# Input_scheme.net
KiCad netlist of a schematic drawn in Altium Designer
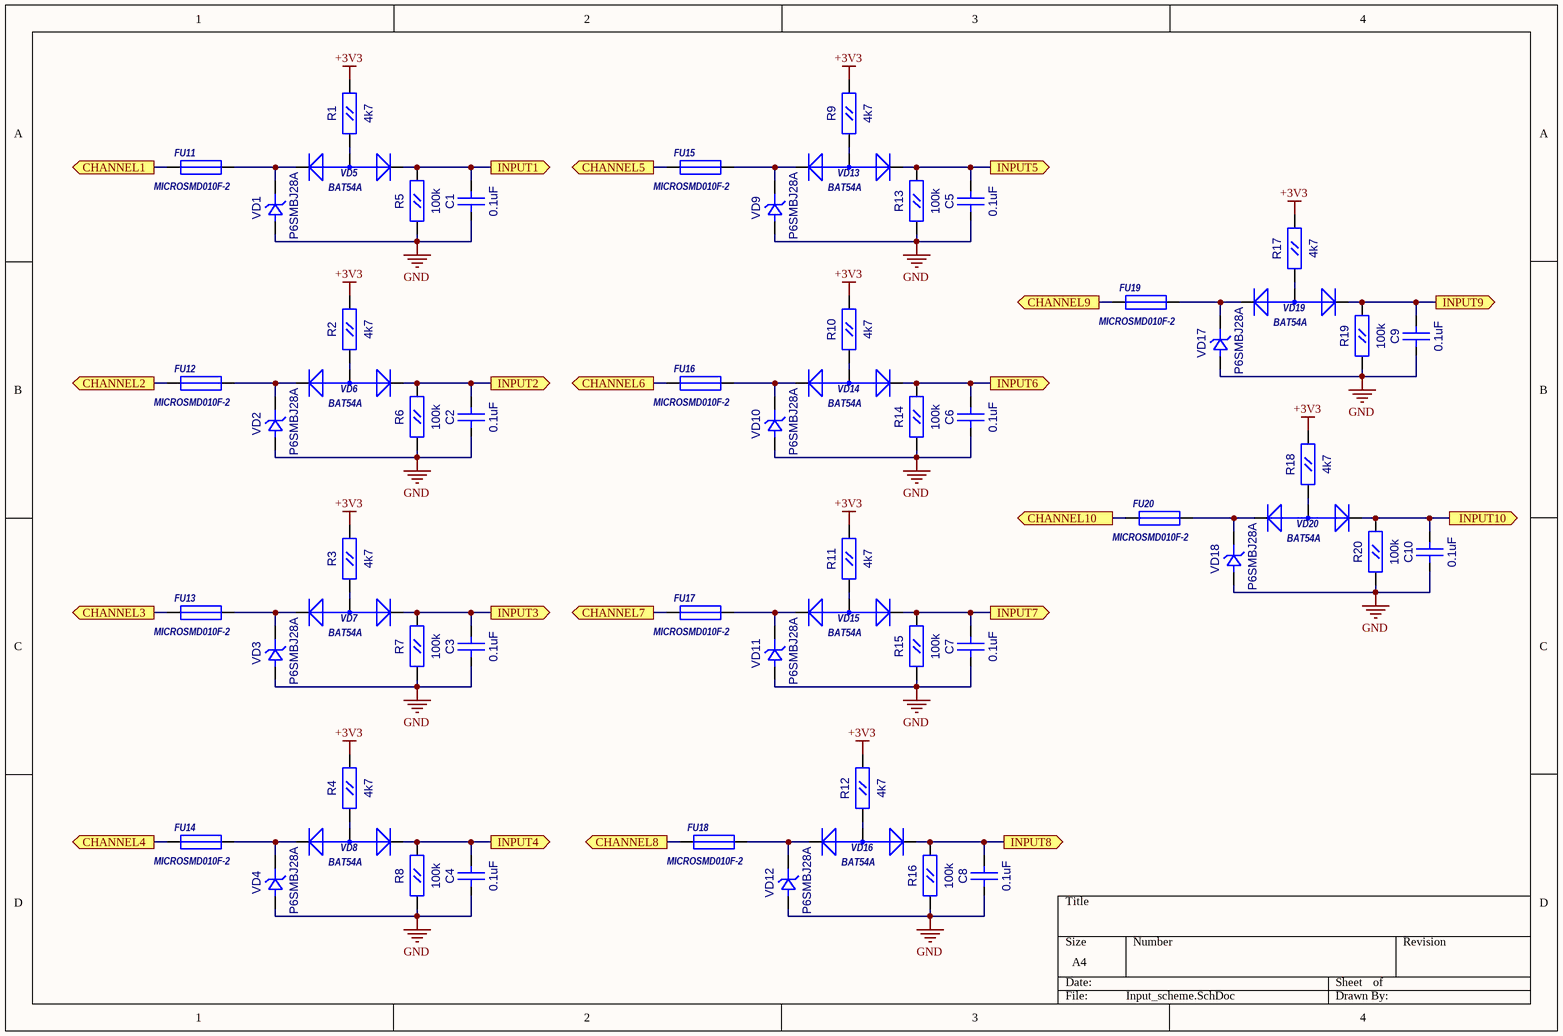
[diagram p0: Input_scheme.SchDoc]

(export (version "E")
  (design (tool "Eeschema 10.0.6"))
  (components
    (comp (ref "C1")
      (value "0.1uF")
      (footprint "CC0603")
      (description "CC0603")
      (libsource (lib "gprs_modem_2") (part "CC0603"))
    )
    (comp (ref "C2")
      (value "0.1uF")
      (footprint "CC0603")
      (description "CC0603")
      (libsource (lib "gprs_modem_2") (part "CC0603"))
    )
    (comp (ref "C3")
      (value "0.1uF")
      (footprint "CC0603")
      (description "CC0603")
      (libsource (lib "gprs_modem_2") (part "CC0603"))
    )
    (comp (ref "C4")
      (value "0.1uF")
      (footprint "CC0603")
      (description "CC0603")
      (libsource (lib "gprs_modem_2") (part "CC0603"))
    )
    (comp (ref "C5")
      (value "0.1uF")
      (footprint "CC0603")
      (description "CC0603")
      (libsource (lib "gprs_modem_2") (part "CC0603"))
    )
    (comp (ref "C6")
      (value "0.1uF")
      (footprint "CC0603")
      (description "CC0603")
      (libsource (lib "gprs_modem_2") (part "CC0603"))
    )
    (comp (ref "C7")
      (value "0.1uF")
      (footprint "CC0603")
      (description "CC0603")
      (libsource (lib "gprs_modem_2") (part "CC0603"))
    )
    (comp (ref "C8")
      (value "0.1uF")
      (footprint "CC0603")
      (description "CC0603")
      (libsource (lib "gprs_modem_2") (part "CC0603"))
    )
    (comp (ref "C9")
      (value "0.1uF")
      (footprint "CC0603")
      (description "CC0603")
      (libsource (lib "gprs_modem_2") (part "CC0603"))
    )
    (comp (ref "C10")
      (value "0.1uF")
      (footprint "CC0603")
      (description "CC0603")
      (libsource (lib "gprs_modem_2") (part "CC0603"))
    )
    (comp (ref "FU11")
      (value "MICROSMD010F-2")
      (footprint "RC1210")
      (description "MICROSMD")
      (libsource (lib "gprs_modem_2") (part "MICROSMD"))
    )
    (comp (ref "FU12")
      (value "MICROSMD010F-2")
      (footprint "RC1210")
      (description "MICROSMD")
      (libsource (lib "gprs_modem_2") (part "MICROSMD"))
    )
    (comp (ref "FU13")
      (value "MICROSMD010F-2")
      (footprint "RC1210")
      (description "MICROSMD")
      (libsource (lib "gprs_modem_2") (part "MICROSMD"))
    )
    (comp (ref "FU14")
      (value "MICROSMD010F-2")
      (footprint "RC1210")
      (description "MICROSMD")
      (libsource (lib "gprs_modem_2") (part "MICROSMD"))
    )
    (comp (ref "FU15")
      (value "MICROSMD010F-2")
      (footprint "RC1210")
      (description "MICROSMD")
      (libsource (lib "gprs_modem_2") (part "MICROSMD"))
    )
    (comp (ref "FU16")
      (value "MICROSMD010F-2")
      (footprint "RC1210")
      (description "MICROSMD")
      (libsource (lib "gprs_modem_2") (part "MICROSMD"))
    )
    (comp (ref "FU17")
      (value "MICROSMD010F-2")
      (footprint "RC1210")
      (description "MICROSMD")
      (libsource (lib "gprs_modem_2") (part "MICROSMD"))
    )
    (comp (ref "FU18")
      (value "MICROSMD010F-2")
      (footprint "RC1210")
      (description "MICROSMD")
      (libsource (lib "gprs_modem_2") (part "MICROSMD"))
    )
    (comp (ref "FU19")
      (value "MICROSMD010F-2")
      (footprint "RC1210")
      (description "MICROSMD")
      (libsource (lib "gprs_modem_2") (part "MICROSMD"))
    )
    (comp (ref "FU20")
      (value "MICROSMD010F-2")
      (footprint "RC1210")
      (description "MICROSMD")
      (libsource (lib "gprs_modem_2") (part "MICROSMD"))
    )
    (comp (ref "R1")
      (value "4k7")
      (footprint "RC0603")
      (description "RC0603")
      (libsource (lib "gprs_modem_2") (part "RC0603"))
    )
    (comp (ref "R2")
      (value "4k7")
      (footprint "RC0603")
      (description "RC0603")
      (libsource (lib "gprs_modem_2") (part "RC0603"))
    )
    (comp (ref "R3")
      (value "4k7")
      (footprint "RC0603")
      (description "RC0603")
      (libsource (lib "gprs_modem_2") (part "RC0603"))
    )
    (comp (ref "R4")
      (value "4k7")
      (footprint "RC0603")
      (description "RC0603")
      (libsource (lib "gprs_modem_2") (part "RC0603"))
    )
    (comp (ref "R5")
      (value "100k")
      (footprint "RC0603")
      (description "RC0603")
      (libsource (lib "gprs_modem_2") (part "RC0603"))
    )
    (comp (ref "R6")
      (value "100k")
      (footprint "RC0603")
      (description "RC0603")
      (libsource (lib "gprs_modem_2") (part "RC0603"))
    )
    (comp (ref "R7")
      (value "100k")
      (footprint "RC0603")
      (description "RC0603")
      (libsource (lib "gprs_modem_2") (part "RC0603"))
    )
    (comp (ref "R8")
      (value "100k")
      (footprint "RC0603")
      (description "RC0603")
      (libsource (lib "gprs_modem_2") (part "RC0603"))
    )
    (comp (ref "R9")
      (value "4k7")
      (footprint "RC0603")
      (description "RC0603")
      (libsource (lib "gprs_modem_2") (part "RC0603"))
    )
    (comp (ref "R10")
      (value "4k7")
      (footprint "RC0603")
      (description "RC0603")
      (libsource (lib "gprs_modem_2") (part "RC0603"))
    )
    (comp (ref "R11")
      (value "4k7")
      (footprint "RC0603")
      (description "RC0603")
      (libsource (lib "gprs_modem_2") (part "RC0603"))
    )
    (comp (ref "R12")
      (value "4k7")
      (footprint "RC0603")
      (description "RC0603")
      (libsource (lib "gprs_modem_2") (part "RC0603"))
    )
    (comp (ref "R13")
      (value "100k")
      (footprint "RC0603")
      (description "RC0603")
      (libsource (lib "gprs_modem_2") (part "RC0603"))
    )
    (comp (ref "R14")
      (value "100k")
      (footprint "RC0603")
      (description "RC0603")
      (libsource (lib "gprs_modem_2") (part "RC0603"))
    )
    (comp (ref "R15")
      (value "100k")
      (footprint "RC0603")
      (description "RC0603")
      (libsource (lib "gprs_modem_2") (part "RC0603"))
    )
    (comp (ref "R16")
      (value "100k")
      (footprint "RC0603")
      (description "RC0603")
      (libsource (lib "gprs_modem_2") (part "RC0603"))
    )
    (comp (ref "R17")
      (value "4k7")
      (footprint "RC0603")
      (description "RC0603")
      (libsource (lib "gprs_modem_2") (part "RC0603"))
    )
    (comp (ref "R18")
      (value "4k7")
      (footprint "RC0603")
      (description "RC0603")
      (libsource (lib "gprs_modem_2") (part "RC0603"))
    )
    (comp (ref "R19")
      (value "100k")
      (footprint "RC0603")
      (description "RC0603")
      (libsource (lib "gprs_modem_2") (part "RC0603"))
    )
    (comp (ref "R20")
      (value "100k")
      (footprint "RC0603")
      (description "RC0603")
      (libsource (lib "gprs_modem_2") (part "RC0603"))
    )
    (comp (ref "VD1")
      (value "P6SMBJ28A")
      (footprint "SMB")
      (description "SMBJ")
      (libsource (lib "gprs_modem") (part "SMBJ"))
    )
    (comp (ref "VD2")
      (value "P6SMBJ28A")
      (footprint "SMB")
      (description "SMBJ")
      (libsource (lib "gprs_modem") (part "SMBJ"))
    )
    (comp (ref "VD3")
      (value "P6SMBJ28A")
      (footprint "SMB")
      (description "SMBJ")
      (libsource (lib "gprs_modem") (part "SMBJ"))
    )
    (comp (ref "VD4")
      (value "P6SMBJ28A")
      (footprint "SMB")
      (description "SMBJ")
      (libsource (lib "gprs_modem") (part "SMBJ"))
    )
    (comp (ref "VD5") (value "BAT54A") (footprint "SOT-23(123)") (libsource (lib "*") (part "BAT54A")))
    (comp (ref "VD6") (value "BAT54A") (footprint "SOT-23(123)") (libsource (lib "*") (part "BAT54A")))
    (comp (ref "VD7") (value "BAT54A") (footprint "SOT-23(123)") (libsource (lib "*") (part "BAT54A")))
    (comp (ref "VD8") (value "BAT54A") (footprint "SOT-23(123)") (libsource (lib "*") (part "BAT54A")))
    (comp (ref "VD9")
      (value "P6SMBJ28A")
      (footprint "SMB")
      (description "SMBJ")
      (libsource (lib "gprs_modem") (part "SMBJ"))
    )
    (comp (ref "VD10")
      (value "P6SMBJ28A")
      (footprint "SMB")
      (description "SMBJ")
      (libsource (lib "gprs_modem") (part "SMBJ"))
    )
    (comp (ref "VD11")
      (value "P6SMBJ28A")
      (footprint "SMB")
      (description "SMBJ")
      (libsource (lib "gprs_modem") (part "SMBJ"))
    )
    (comp (ref "VD12")
      (value "P6SMBJ28A")
      (footprint "SMB")
      (description "SMBJ")
      (libsource (lib "gprs_modem") (part "SMBJ"))
    )
    (comp (ref "VD13") (value "BAT54A") (footprint "SOT-23(123)") (libsource (lib "*") (part "BAT54A")))
    (comp (ref "VD14") (value "BAT54A") (footprint "SOT-23(123)") (libsource (lib "*") (part "BAT54A")))
    (comp (ref "VD15") (value "BAT54A") (footprint "SOT-23(123)") (libsource (lib "*") (part "BAT54A")))
    (comp (ref "VD16") (value "BAT54A") (footprint "SOT-23(123)") (libsource (lib "*") (part "BAT54A")))
    (comp (ref "VD17")
      (value "P6SMBJ28A")
      (footprint "SMB")
      (description "SMBJ")
      (libsource (lib "gprs_modem") (part "SMBJ"))
    )
    (comp (ref "VD18")
      (value "P6SMBJ28A")
      (footprint "SMB")
      (description "SMBJ")
      (libsource (lib "gprs_modem") (part "SMBJ"))
    )
    (comp (ref "VD19") (value "BAT54A") (footprint "SOT-23(123)") (libsource (lib "*") (part "BAT54A")))
    (comp (ref "VD20") (value "BAT54A") (footprint "SOT-23(123)") (libsource (lib "*") (part "BAT54A")))
  )
  (nets
    (net (code "1") (name "+3V3") (class "Default")
      (node (ref "R1") (pin "2") (pinfunction "B_2") (pintype "passive"))
      (node (ref "R10") (pin "2") (pinfunction "B_2") (pintype "passive"))
      (node (ref "R11") (pin "2") (pinfunction "B_2") (pintype "passive"))
      (node (ref "R12") (pin "2") (pinfunction "B_2") (pintype "passive"))
      (node (ref "R17") (pin "2") (pinfunction "B_2") (pintype "passive"))
      (node (ref "R18") (pin "2") (pinfunction "B_2") (pintype "passive"))
      (node (ref "R2") (pin "2") (pinfunction "B_2") (pintype "passive"))
      (node (ref "R3") (pin "2") (pinfunction "B_2") (pintype "passive"))
      (node (ref "R4") (pin "2") (pinfunction "B_2") (pintype "passive"))
      (node (ref "R9") (pin "2") (pinfunction "B_2") (pintype "passive"))
    )
    (net (code "2") (name "/CHANNEL1") (class "Default") (node (ref "FU11") (pin "1") (pintype "passive")))
    (net (code "3") (name "/CHANNEL2") (class "Default") (node (ref "FU12") (pin "1") (pintype "passive")))
    (net (code "4") (name "/CHANNEL3") (class "Default") (node (ref "FU13") (pin "1") (pintype "passive")))
    (net (code "5") (name "/CHANNEL4") (class "Default") (node (ref "FU14") (pin "1") (pintype "passive")))
    (net (code "6") (name "/CHANNEL5") (class "Default") (node (ref "FU15") (pin "1") (pintype "passive")))
    (net (code "7") (name "/CHANNEL6") (class "Default") (node (ref "FU16") (pin "1") (pintype "passive")))
    (net (code "8") (name "/CHANNEL7") (class "Default") (node (ref "FU17") (pin "1") (pintype "passive")))
    (net (code "9") (name "/CHANNEL8") (class "Default") (node (ref "FU18") (pin "1") (pintype "passive")))
    (net (code "10") (name "/CHANNEL9") (class "Default") (node (ref "FU19") (pin "1") (pintype "passive")))
    (net (code "11") (name "/CHANNEL10") (class "Default") (node (ref "FU20") (pin "1") (pintype "passive")))
    (net (code "12") (name "/INPUT1") (class "Default")
      (node (ref "C1") (pin "2") (pinfunction "B_2") (pintype "passive"))
      (node (ref "R5") (pin "2") (pinfunction "B_2") (pintype "passive"))
      (node (ref "VD5") (pin "2") (pinfunction "K_2") (pintype "passive"))
    )
    (net (code "13") (name "/INPUT2") (class "Default")
      (node (ref "C2") (pin "2") (pinfunction "B_2") (pintype "passive"))
      (node (ref "R6") (pin "2") (pinfunction "B_2") (pintype "passive"))
      (node (ref "VD6") (pin "2") (pinfunction "K_2") (pintype "passive"))
    )
    (net (code "14") (name "/INPUT3") (class "Default")
      (node (ref "C3") (pin "2") (pinfunction "B_2") (pintype "passive"))
      (node (ref "R7") (pin "2") (pinfunction "B_2") (pintype "passive"))
      (node (ref "VD7") (pin "2") (pinfunction "K_2") (pintype "passive"))
    )
    (net (code "15") (name "/INPUT4") (class "Default")
      (node (ref "C4") (pin "2") (pinfunction "B_2") (pintype "passive"))
      (node (ref "R8") (pin "2") (pinfunction "B_2") (pintype "passive"))
      (node (ref "VD8") (pin "2") (pinfunction "K_2") (pintype "passive"))
    )
    (net (code "16") (name "/INPUT5") (class "Default")
      (node (ref "C5") (pin "2") (pinfunction "B_2") (pintype "passive"))
      (node (ref "R13") (pin "2") (pinfunction "B_2") (pintype "passive"))
      (node (ref "VD13") (pin "2") (pinfunction "K_2") (pintype "passive"))
    )
    (net (code "17") (name "/INPUT6") (class "Default")
      (node (ref "C6") (pin "2") (pinfunction "B_2") (pintype "passive"))
      (node (ref "R14") (pin "2") (pinfunction "B_2") (pintype "passive"))
      (node (ref "VD14") (pin "2") (pinfunction "K_2") (pintype "passive"))
    )
    (net (code "18") (name "/INPUT7") (class "Default")
      (node (ref "C7") (pin "2") (pinfunction "B_2") (pintype "passive"))
      (node (ref "R15") (pin "2") (pinfunction "B_2") (pintype "passive"))
      (node (ref "VD15") (pin "2") (pinfunction "K_2") (pintype "passive"))
    )
    (net (code "19") (name "/INPUT8") (class "Default")
      (node (ref "C8") (pin "2") (pinfunction "B_2") (pintype "passive"))
      (node (ref "R16") (pin "2") (pinfunction "B_2") (pintype "passive"))
      (node (ref "VD16") (pin "2") (pinfunction "K_2") (pintype "passive"))
    )
    (net (code "20") (name "/INPUT9") (class "Default")
      (node (ref "C9") (pin "2") (pinfunction "B_2") (pintype "passive"))
      (node (ref "R19") (pin "2") (pinfunction "B_2") (pintype "passive"))
      (node (ref "VD19") (pin "2") (pinfunction "K_2") (pintype "passive"))
    )
    (net (code "21") (name "/INPUT10") (class "Default")
      (node (ref "C10") (pin "2") (pinfunction "B_2") (pintype "passive"))
      (node (ref "R20") (pin "2") (pinfunction "B_2") (pintype "passive"))
      (node (ref "VD20") (pin "2") (pinfunction "K_2") (pintype "passive"))
    )
    (net (code "22") (name "GND") (class "Default")
      (node (ref "C1") (pin "1") (pinfunction "A_1") (pintype "passive"))
      (node (ref "C10") (pin "1") (pinfunction "A_1") (pintype "passive"))
      (node (ref "C2") (pin "1") (pinfunction "A_1") (pintype "passive"))
      (node (ref "C3") (pin "1") (pinfunction "A_1") (pintype "passive"))
      (node (ref "C4") (pin "1") (pinfunction "A_1") (pintype "passive"))
      (node (ref "C5") (pin "1") (pinfunction "A_1") (pintype "passive"))
      (node (ref "C6") (pin "1") (pinfunction "A_1") (pintype "passive"))
      (node (ref "C7") (pin "1") (pinfunction "A_1") (pintype "passive"))
      (node (ref "C8") (pin "1") (pinfunction "A_1") (pintype "passive"))
      (node (ref "C9") (pin "1") (pinfunction "A_1") (pintype "passive"))
      (node (ref "R13") (pin "1") (pinfunction "A_1") (pintype "passive"))
      (node (ref "R14") (pin "1") (pinfunction "A_1") (pintype "passive"))
      (node (ref "R15") (pin "1") (pinfunction "A_1") (pintype "passive"))
      (node (ref "R16") (pin "1") (pinfunction "A_1") (pintype "passive"))
      (node (ref "R19") (pin "1") (pinfunction "A_1") (pintype "passive"))
      (node (ref "R20") (pin "1") (pinfunction "A_1") (pintype "passive"))
      (node (ref "R5") (pin "1") (pinfunction "A_1") (pintype "passive"))
      (node (ref "R6") (pin "1") (pinfunction "A_1") (pintype "passive"))
      (node (ref "R7") (pin "1") (pinfunction "A_1") (pintype "passive"))
      (node (ref "R8") (pin "1") (pinfunction "A_1") (pintype "passive"))
      (node (ref "VD1") (pin "1") (pinfunction "A_1") (pintype "passive"))
      (node (ref "VD10") (pin "1") (pinfunction "A_1") (pintype "passive"))
      (node (ref "VD11") (pin "1") (pinfunction "A_1") (pintype "passive"))
      (node (ref "VD12") (pin "1") (pinfunction "A_1") (pintype "passive"))
      (node (ref "VD17") (pin "1") (pinfunction "A_1") (pintype "passive"))
      (node (ref "VD18") (pin "1") (pinfunction "A_1") (pintype "passive"))
      (node (ref "VD2") (pin "1") (pinfunction "A_1") (pintype "passive"))
      (node (ref "VD3") (pin "1") (pinfunction "A_1") (pintype "passive"))
      (node (ref "VD4") (pin "1") (pinfunction "A_1") (pintype "passive"))
      (node (ref "VD9") (pin "1") (pinfunction "A_1") (pintype "passive"))
    )
    (net (code "23") (name "Net-(R1-A)") (class "Default")
      (node (ref "R1") (pin "1") (pinfunction "A_1") (pintype "passive"))
      (node (ref "VD5") (pin "3") (pinfunction "A_3") (pintype "passive"))
    )
    (net (code "24") (name "Net-(R2-A)") (class "Default")
      (node (ref "R2") (pin "1") (pinfunction "A_1") (pintype "passive"))
      (node (ref "VD6") (pin "3") (pinfunction "A_3") (pintype "passive"))
    )
    (net (code "25") (name "Net-(R3-A)") (class "Default")
      (node (ref "R3") (pin "1") (pinfunction "A_1") (pintype "passive"))
      (node (ref "VD7") (pin "3") (pinfunction "A_3") (pintype "passive"))
    )
    (net (code "26") (name "Net-(R4-A)") (class "Default")
      (node (ref "R4") (pin "1") (pinfunction "A_1") (pintype "passive"))
      (node (ref "VD8") (pin "3") (pinfunction "A_3") (pintype "passive"))
    )
    (net (code "27") (name "Net-(R9-A)") (class "Default")
      (node (ref "R9") (pin "1") (pinfunction "A_1") (pintype "passive"))
      (node (ref "VD13") (pin "3") (pinfunction "A_3") (pintype "passive"))
    )
    (net (code "28") (name "Net-(R10-A)") (class "Default")
      (node (ref "R10") (pin "1") (pinfunction "A_1") (pintype "passive"))
      (node (ref "VD14") (pin "3") (pinfunction "A_3") (pintype "passive"))
    )
    (net (code "29") (name "Net-(R11-A)") (class "Default")
      (node (ref "R11") (pin "1") (pinfunction "A_1") (pintype "passive"))
      (node (ref "VD15") (pin "3") (pinfunction "A_3") (pintype "passive"))
    )
    (net (code "30") (name "Net-(R12-A)") (class "Default")
      (node (ref "R12") (pin "1") (pinfunction "A_1") (pintype "passive"))
      (node (ref "VD16") (pin "3") (pinfunction "A_3") (pintype "passive"))
    )
    (net (code "31") (name "Net-(R17-A)") (class "Default")
      (node (ref "R17") (pin "1") (pinfunction "A_1") (pintype "passive"))
      (node (ref "VD19") (pin "3") (pinfunction "A_3") (pintype "passive"))
    )
    (net (code "32") (name "Net-(R18-A)") (class "Default")
      (node (ref "R18") (pin "1") (pinfunction "A_1") (pintype "passive"))
      (node (ref "VD20") (pin "3") (pinfunction "A_3") (pintype "passive"))
    )
    (net (code "33") (name "Net-(VD1-K)") (class "Default")
      (node (ref "FU11") (pin "2") (pintype "passive"))
      (node (ref "VD1") (pin "2") (pinfunction "K_2") (pintype "passive"))
      (node (ref "VD5") (pin "1") (pinfunction "K_1") (pintype "passive"))
    )
    (net (code "34") (name "Net-(VD2-K)") (class "Default")
      (node (ref "FU12") (pin "2") (pintype "passive"))
      (node (ref "VD2") (pin "2") (pinfunction "K_2") (pintype "passive"))
      (node (ref "VD6") (pin "1") (pinfunction "K_1") (pintype "passive"))
    )
    (net (code "35") (name "Net-(VD3-K)") (class "Default")
      (node (ref "FU13") (pin "2") (pintype "passive"))
      (node (ref "VD3") (pin "2") (pinfunction "K_2") (pintype "passive"))
      (node (ref "VD7") (pin "1") (pinfunction "K_1") (pintype "passive"))
    )
    (net (code "36") (name "Net-(VD4-K)") (class "Default")
      (node (ref "FU14") (pin "2") (pintype "passive"))
      (node (ref "VD4") (pin "2") (pinfunction "K_2") (pintype "passive"))
      (node (ref "VD8") (pin "1") (pinfunction "K_1") (pintype "passive"))
    )
    (net (code "37") (name "Net-(VD9-K)") (class "Default")
      (node (ref "FU15") (pin "2") (pintype "passive"))
      (node (ref "VD13") (pin "1") (pinfunction "K_1") (pintype "passive"))
      (node (ref "VD9") (pin "2") (pinfunction "K_2") (pintype "passive"))
    )
    (net (code "38") (name "Net-(VD10-K)") (class "Default")
      (node (ref "FU16") (pin "2") (pintype "passive"))
      (node (ref "VD10") (pin "2") (pinfunction "K_2") (pintype "passive"))
      (node (ref "VD14") (pin "1") (pinfunction "K_1") (pintype "passive"))
    )
    (net (code "39") (name "Net-(VD11-K)") (class "Default")
      (node (ref "FU17") (pin "2") (pintype "passive"))
      (node (ref "VD11") (pin "2") (pinfunction "K_2") (pintype "passive"))
      (node (ref "VD15") (pin "1") (pinfunction "K_1") (pintype "passive"))
    )
    (net (code "40") (name "Net-(VD12-K)") (class "Default")
      (node (ref "FU18") (pin "2") (pintype "passive"))
      (node (ref "VD12") (pin "2") (pinfunction "K_2") (pintype "passive"))
      (node (ref "VD16") (pin "1") (pinfunction "K_1") (pintype "passive"))
    )
    (net (code "41") (name "Net-(VD17-K)") (class "Default")
      (node (ref "FU19") (pin "2") (pintype "passive"))
      (node (ref "VD17") (pin "2") (pinfunction "K_2") (pintype "passive"))
      (node (ref "VD19") (pin "1") (pinfunction "K_1") (pintype "passive"))
    )
    (net (code "42") (name "Net-(VD18-K)") (class "Default")
      (node (ref "FU20") (pin "2") (pintype "passive"))
      (node (ref "VD18") (pin "2") (pinfunction "K_2") (pintype "passive"))
      (node (ref "VD20") (pin "1") (pinfunction "K_1") (pintype "passive"))
    )
  )
)
